# platform_all1.net
KiCad netlist of a schematic drawn in EAGLE
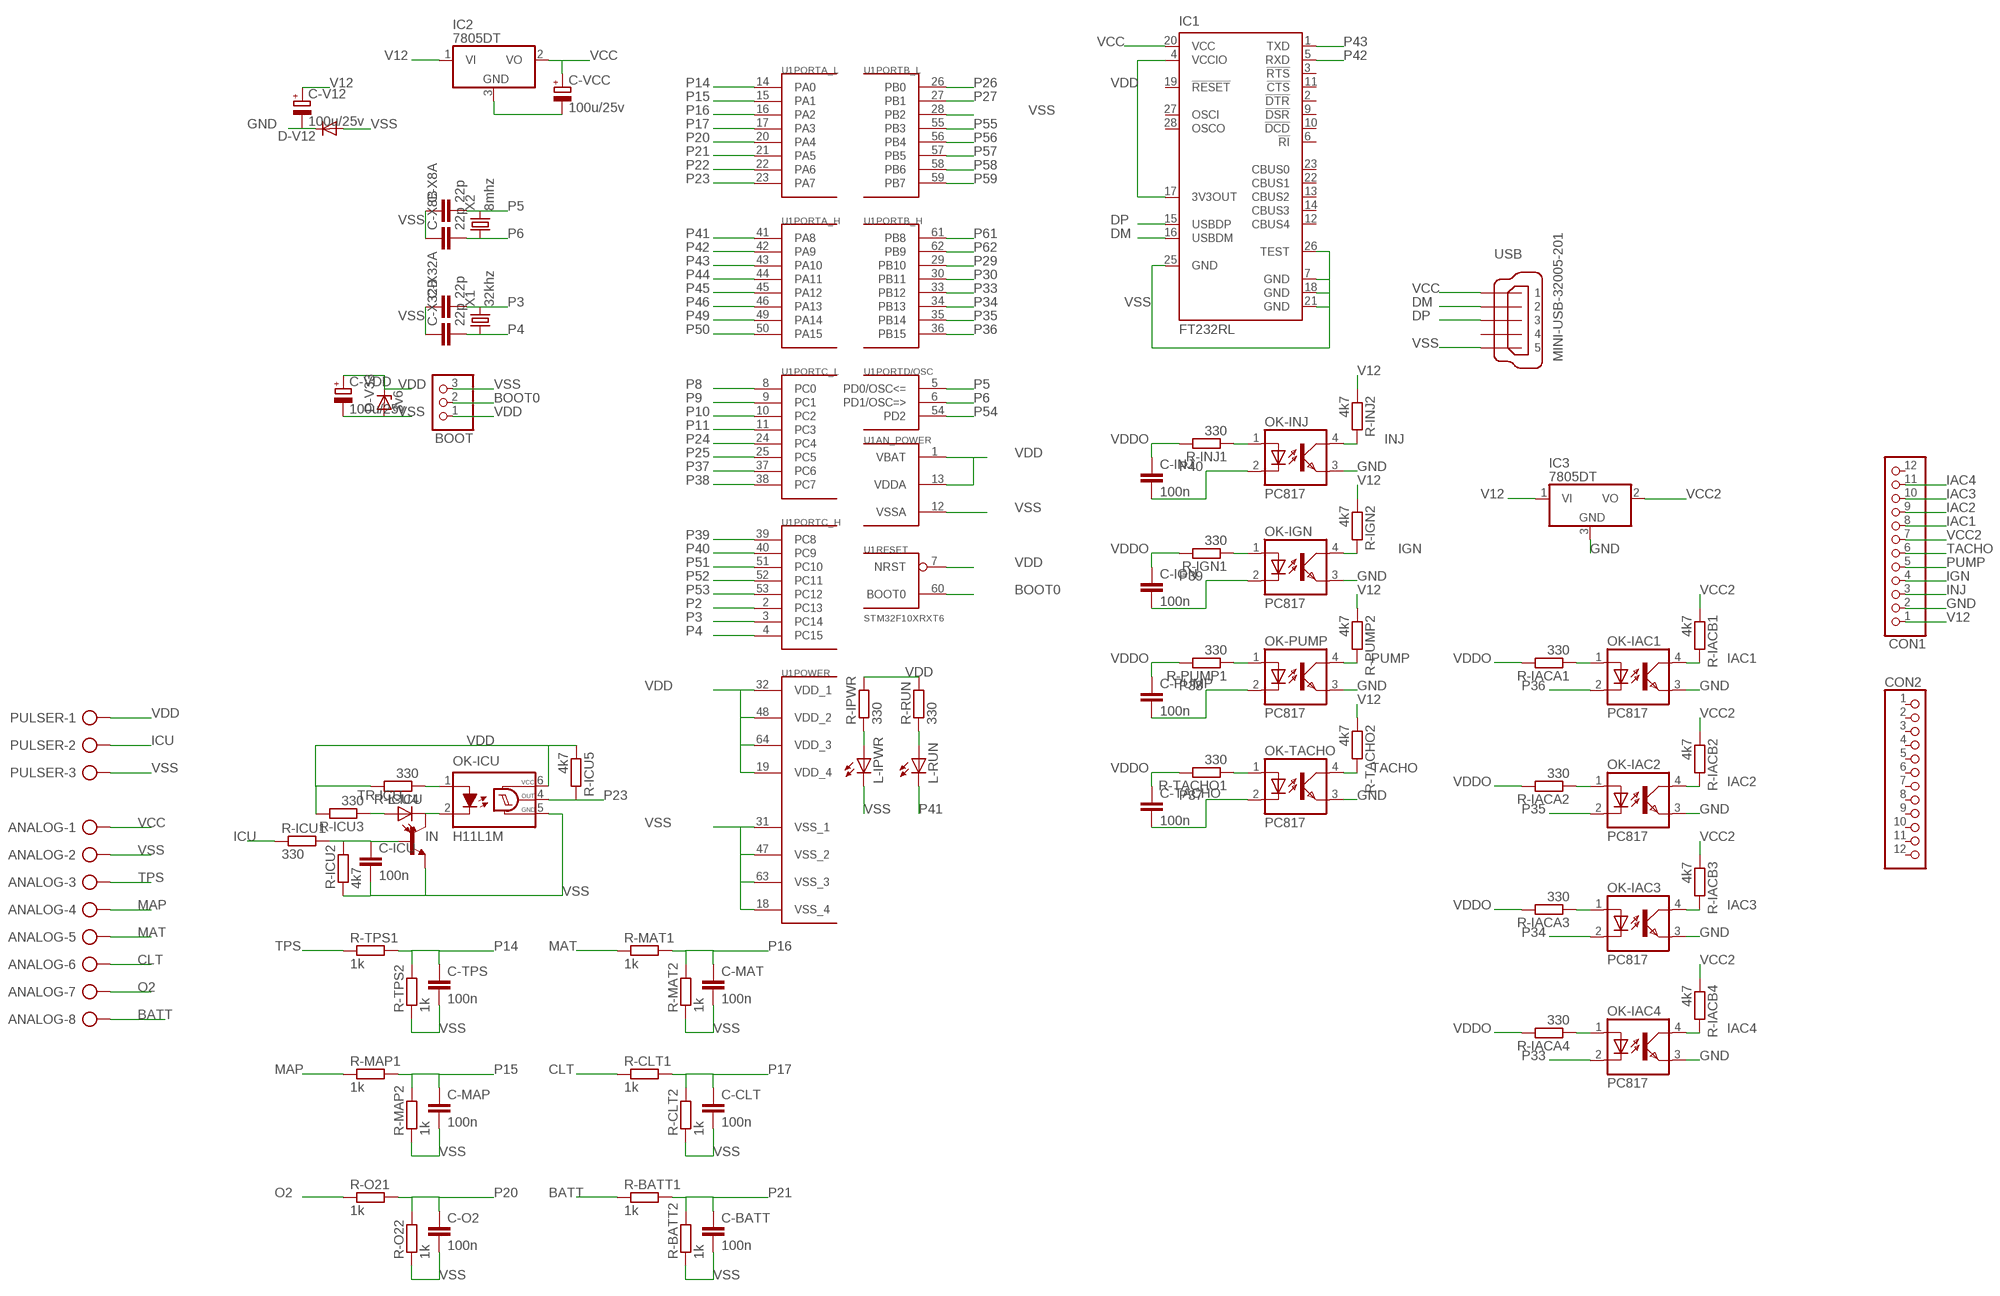
[diagram p0: schematic, sheet 1]

(export (version "E")
  (design (tool "Eeschema 10.0.6"))
  (components
    (comp (ref "ANALOG")
      (value "AK300/8")
      (footprint "eagle-import:AK300_8")
      (libsource (lib "eagle-import") (part "AK300/8"))
    )
    (comp (ref "BOOT")
      (value "PINHD-1X3")
      (footprint "eagle-import:1X03")
      (libsource (lib "eagle-import") (part "PINHD-1X3"))
    )
    (comp (ref "C-BATT")
      (value "100n")
      (footprint "eagle-import:C1206")
      (libsource (lib "eagle-import") (part "C-EUC1206"))
    )
    (comp (ref "C-CLT")
      (value "100n")
      (footprint "eagle-import:C1206")
      (libsource (lib "eagle-import") (part "C-EUC1206"))
    )
    (comp (ref "C-ICU")
      (value "100n")
      (footprint "eagle-import:C1206")
      (libsource (lib "eagle-import") (part "C-EUC1206"))
    )
    (comp (ref "C-IGN")
      (value "100n")
      (footprint "eagle-import:C1206")
      (libsource (lib "eagle-import") (part "C-EUC1206"))
    )
    (comp (ref "C-INJ")
      (value "100n")
      (footprint "eagle-import:C1206")
      (libsource (lib "eagle-import") (part "C-EUC1206"))
    )
    (comp (ref "C-MAP")
      (value "100n")
      (footprint "eagle-import:C1206")
      (libsource (lib "eagle-import") (part "C-EUC1206"))
    )
    (comp (ref "C-MAT")
      (value "100n")
      (footprint "eagle-import:C1206")
      (libsource (lib "eagle-import") (part "C-EUC1206"))
    )
    (comp (ref "C-O2")
      (value "100n")
      (footprint "eagle-import:C1206")
      (libsource (lib "eagle-import") (part "C-EUC1206"))
    )
    (comp (ref "C-PUMP")
      (value "100n")
      (footprint "eagle-import:C1206")
      (libsource (lib "eagle-import") (part "C-EUC1206"))
    )
    (comp (ref "C-TACHO")
      (value "100n")
      (footprint "eagle-import:C1206")
      (libsource (lib "eagle-import") (part "C-EUC1206"))
    )
    (comp (ref "C-TPS")
      (value "100n")
      (footprint "eagle-import:C1206")
      (libsource (lib "eagle-import") (part "C-EUC1206"))
    )
    (comp (ref "C-V12")
      (value "100u/25v")
      (footprint "eagle-import:PANASONIC_D")
      (libsource (lib "eagle-import") (part "CPOL-EUD"))
    )
    (comp (ref "C-VCC")
      (value "100u/25v")
      (footprint "eagle-import:PANASONIC_D")
      (libsource (lib "eagle-import") (part "CPOL-EUD"))
    )
    (comp (ref "C-VDD")
      (value "100u/25v")
      (footprint "eagle-import:PANASONIC_D")
      (libsource (lib "eagle-import") (part "CPOL-EUD"))
    )
    (comp (ref "C-X8A")
      (value "22p")
      (footprint "eagle-import:C1206")
      (libsource (lib "eagle-import") (part "C-EUC1206"))
    )
    (comp (ref "C-X8B")
      (value "22p")
      (footprint "eagle-import:C1206")
      (libsource (lib "eagle-import") (part "C-EUC1206"))
    )
    (comp (ref "C-X32A")
      (value "22p")
      (footprint "eagle-import:C1206")
      (libsource (lib "eagle-import") (part "C-EUC1206"))
    )
    (comp (ref "C-X32B")
      (value "22p")
      (footprint "eagle-import:C1206")
      (libsource (lib "eagle-import") (part "C-EUC1206"))
    )
    (comp (ref "CON1")
      (value "PINHD-1X12")
      (footprint "eagle-import:1X12")
      (libsource (lib "eagle-import") (part "PINHD-1X12"))
    )
    (comp (ref "CON2")
      (value "PINHD-1X12")
      (footprint "eagle-import:1X12")
      (libsource (lib "eagle-import") (part "PINHD-1X12"))
    )
    (comp (ref "D-V12")
      (value "DIODE-SMB")
      (footprint "eagle-import:SMB")
      (libsource (lib "eagle-import") (part "DIODE-SMB"))
    )
    (comp (ref "D-V33")
      (value "3v6")
      (footprint "eagle-import:SMB")
      (libsource (lib "eagle-import") (part "ZENER-DIODESMB"))
    )
    (comp (ref "IC1")
      (value "FT232RL")
      (footprint "eagle-import:SSOP28")
      (libsource (lib "eagle-import") (part "FT232RL"))
    )
    (comp (ref "IC2")
      (value "7805DT")
      (footprint "eagle-import:TO252")
      (libsource (lib "eagle-import") (part "78DT05"))
    )
    (comp (ref "IC3")
      (value "7805DT")
      (footprint "eagle-import:TO252")
      (libsource (lib "eagle-import") (part "78DT05"))
    )
    (comp (ref "L-ICU")
      (value "LEDSMT1206")
      (footprint "eagle-import:1206")
      (libsource (lib "eagle-import") (part "LEDSMT1206"))
    )
    (comp (ref "L-IPWR")
      (value "LEDSMT1206")
      (footprint "eagle-import:1206")
      (libsource (lib "eagle-import") (part "LEDSMT1206"))
    )
    (comp (ref "L-RUN")
      (value "LEDSMT1206")
      (footprint "eagle-import:1206")
      (libsource (lib "eagle-import") (part "LEDSMT1206"))
    )
    (comp (ref "OK-IAC1")
      (value "PC817")
      (footprint "eagle-import:DIL04")
      (fields (field (name "MPN") "PC817X4J000F"))
      (libsource (lib "eagle-import") (part "PC817"))
    )
    (comp (ref "OK-IAC2")
      (value "PC817")
      (footprint "eagle-import:DIL04")
      (fields (field (name "MPN") "PC817X4J000F"))
      (libsource (lib "eagle-import") (part "PC817"))
    )
    (comp (ref "OK-IAC3")
      (value "PC817")
      (footprint "eagle-import:DIL04")
      (fields (field (name "MPN") "PC817X4J000F"))
      (libsource (lib "eagle-import") (part "PC817"))
    )
    (comp (ref "OK-IAC4")
      (value "PC817")
      (footprint "eagle-import:DIL04")
      (fields (field (name "MPN") "PC817X4J000F"))
      (libsource (lib "eagle-import") (part "PC817"))
    )
    (comp (ref "OK-ICU")
      (value "H11L1M")
      (footprint "eagle-import:DIL06")
      (fields (field (name "MF") "FAIRCHILD SEMICONDUCTOR") (field (name "MPN") "H11L1-M"))
      (libsource (lib "eagle-import") (part "H11LM1"))
    )
    (comp (ref "OK-IGN")
      (value "PC817")
      (footprint "eagle-import:DIL04")
      (fields (field (name "MPN") "PC817X4J000F"))
      (libsource (lib "eagle-import") (part "PC817"))
    )
    (comp (ref "OK-INJ")
      (value "PC817")
      (footprint "eagle-import:DIL04")
      (fields (field (name "MPN") "PC817X4J000F"))
      (libsource (lib "eagle-import") (part "PC817"))
    )
    (comp (ref "OK-PUMP")
      (value "PC817")
      (footprint "eagle-import:DIL04")
      (fields (field (name "MPN") "PC817X4J000F"))
      (libsource (lib "eagle-import") (part "PC817"))
    )
    (comp (ref "OK-TACHO")
      (value "PC817")
      (footprint "eagle-import:DIL04")
      (fields (field (name "MPN") "PC817X4J000F"))
      (libsource (lib "eagle-import") (part "PC817"))
    )
    (comp (ref "PULSER")
      (value "AK300/3")
      (footprint "eagle-import:AK300_3")
      (libsource (lib "eagle-import") (part "AK300/3"))
    )
    (comp (ref "R-BATT1")
      (value "1k")
      (footprint "eagle-import:R1206")
      (libsource (lib "eagle-import") (part "R-EU_R1206"))
    )
    (comp (ref "R-BATT2")
      (value "1k")
      (footprint "eagle-import:R1206")
      (libsource (lib "eagle-import") (part "R-EU_R1206"))
    )
    (comp (ref "R-CLT1")
      (value "1k")
      (footprint "eagle-import:R1206")
      (libsource (lib "eagle-import") (part "R-EU_R1206"))
    )
    (comp (ref "R-CLT2")
      (value "1k")
      (footprint "eagle-import:R1206")
      (libsource (lib "eagle-import") (part "R-EU_R1206"))
    )
    (comp (ref "R-IACA1")
      (value "330")
      (footprint "eagle-import:R1206")
      (libsource (lib "eagle-import") (part "R-EU_R1206"))
    )
    (comp (ref "R-IACA2")
      (value "330")
      (footprint "eagle-import:R1206")
      (libsource (lib "eagle-import") (part "R-EU_R1206"))
    )
    (comp (ref "R-IACA3")
      (value "330")
      (footprint "eagle-import:R1206")
      (libsource (lib "eagle-import") (part "R-EU_R1206"))
    )
    (comp (ref "R-IACA4")
      (value "330")
      (footprint "eagle-import:R1206")
      (libsource (lib "eagle-import") (part "R-EU_R1206"))
    )
    (comp (ref "R-IACB1")
      (value "4k7")
      (footprint "eagle-import:R1206")
      (libsource (lib "eagle-import") (part "R-EU_R1206"))
    )
    (comp (ref "R-IACB2")
      (value "4k7")
      (footprint "eagle-import:R1206")
      (libsource (lib "eagle-import") (part "R-EU_R1206"))
    )
    (comp (ref "R-IACB3")
      (value "4k7")
      (footprint "eagle-import:R1206")
      (libsource (lib "eagle-import") (part "R-EU_R1206"))
    )
    (comp (ref "R-IACB4")
      (value "4k7")
      (footprint "eagle-import:R1206")
      (libsource (lib "eagle-import") (part "R-EU_R1206"))
    )
    (comp (ref "R-ICU1")
      (value "330")
      (footprint "eagle-import:R1206")
      (libsource (lib "eagle-import") (part "R-EU_R1206"))
    )
    (comp (ref "R-ICU2")
      (value "4k7")
      (footprint "eagle-import:R1206")
      (libsource (lib "eagle-import") (part "R-EU_R1206"))
    )
    (comp (ref "R-ICU3")
      (value "330")
      (footprint "eagle-import:R1206")
      (libsource (lib "eagle-import") (part "R-EU_R1206"))
    )
    (comp (ref "R-ICU4")
      (value "330")
      (footprint "eagle-import:R1206")
      (libsource (lib "eagle-import") (part "R-EU_R1206"))
    )
    (comp (ref "R-ICU5")
      (value "4k7")
      (footprint "eagle-import:R1206")
      (libsource (lib "eagle-import") (part "R-EU_R1206"))
    )
    (comp (ref "R-IGN1")
      (value "330")
      (footprint "eagle-import:R1206")
      (libsource (lib "eagle-import") (part "R-EU_R1206"))
    )
    (comp (ref "R-IGN2")
      (value "4k7")
      (footprint "eagle-import:R1206")
      (libsource (lib "eagle-import") (part "R-EU_R1206"))
    )
    (comp (ref "R-INJ1")
      (value "330")
      (footprint "eagle-import:R1206")
      (libsource (lib "eagle-import") (part "R-EU_R1206"))
    )
    (comp (ref "R-INJ2")
      (value "4k7")
      (footprint "eagle-import:R1206")
      (libsource (lib "eagle-import") (part "R-EU_R1206"))
    )
    (comp (ref "R-IPWR")
      (value "330")
      (footprint "eagle-import:R1206")
      (libsource (lib "eagle-import") (part "R-EU_R1206"))
    )
    (comp (ref "R-MAP1")
      (value "1k")
      (footprint "eagle-import:R1206")
      (libsource (lib "eagle-import") (part "R-EU_R1206"))
    )
    (comp (ref "R-MAP2")
      (value "1k")
      (footprint "eagle-import:R1206")
      (libsource (lib "eagle-import") (part "R-EU_R1206"))
    )
    (comp (ref "R-MAT1")
      (value "1k")
      (footprint "eagle-import:R1206")
      (libsource (lib "eagle-import") (part "R-EU_R1206"))
    )
    (comp (ref "R-MAT2")
      (value "1k")
      (footprint "eagle-import:R1206")
      (libsource (lib "eagle-import") (part "R-EU_R1206"))
    )
    (comp (ref "R-O21")
      (value "1k")
      (footprint "eagle-import:R1206")
      (libsource (lib "eagle-import") (part "R-EU_R1206"))
    )
    (comp (ref "R-O22")
      (value "1k")
      (footprint "eagle-import:R1206")
      (libsource (lib "eagle-import") (part "R-EU_R1206"))
    )
    (comp (ref "R-PUMP1")
      (value "330")
      (footprint "eagle-import:R1206")
      (libsource (lib "eagle-import") (part "R-EU_R1206"))
    )
    (comp (ref "R-PUMP2")
      (value "4k7")
      (footprint "eagle-import:R1206")
      (libsource (lib "eagle-import") (part "R-EU_R1206"))
    )
    (comp (ref "R-RUN")
      (value "330")
      (footprint "eagle-import:R1206")
      (libsource (lib "eagle-import") (part "R-EU_R1206"))
    )
    (comp (ref "R-TACHO1")
      (value "330")
      (footprint "eagle-import:R1206")
      (libsource (lib "eagle-import") (part "R-EU_R1206"))
    )
    (comp (ref "R-TACHO2")
      (value "4k7")
      (footprint "eagle-import:R1206")
      (libsource (lib "eagle-import") (part "R-EU_R1206"))
    )
    (comp (ref "R-TPS1")
      (value "1k")
      (footprint "eagle-import:R1206")
      (libsource (lib "eagle-import") (part "R-EU_R1206"))
    )
    (comp (ref "R-TPS2")
      (value "1k")
      (footprint "eagle-import:R1206")
      (libsource (lib "eagle-import") (part "R-EU_R1206"))
    )
    (comp (ref "TR-ICU")
      (value "MMBT3904LT1-NPN-SOT23-BEC")
      (footprint "eagle-import:SOT23-BEC")
      (libsource (lib "eagle-import") (part "-NPN-SOT23-BECMMBT3904LT1"))
    )
    (comp (ref "U1")
      (value "STM32F10XRXT6")
      (footprint "eagle-import:TQFP64")
      (libsource (lib "eagle-import") (part "STM32F10XRXT6"))
    )
    (comp (ref "USB")
      (value "MINI-USB-32005-201")
      (footprint "eagle-import:32005-201")
      (libsource (lib "eagle-import") (part "MINI-USB-32005-201"))
    )
    (comp (ref "X1")
      (value "32khz")
      (footprint "eagle-import:TC26V")
      (libsource (lib "eagle-import") (part "CRYSTALTC26V"))
    )
    (comp (ref "X2")
      (value "8mhz")
      (footprint "eagle-import:HC49U-V")
      (libsource (lib "eagle-import") (part "CRYSTALHC49U-V"))
    )
  )
  (nets
    (net (code "1") (name "/BATT") (class "Default")
      (node (ref "ANALOG") (pin "8") (pinfunction "KL_8") (pintype "passive"))
      (node (ref "R-BATT1") (pin "1") (pinfunction "1_1") (pintype "passive"))
    )
    (net (code "2") (name "/BOOT0") (class "Default")
      (node (ref "BOOT") (pin "2") (pinfunction "2_2") (pintype "passive"))
      (node (ref "U1") (pin "60") (pinfunction "BOOT0_60") (pintype "input"))
    )
    (net (code "3") (name "/CLT") (class "Default")
      (node (ref "ANALOG") (pin "6") (pinfunction "KL_6") (pintype "passive"))
      (node (ref "R-CLT1") (pin "1") (pinfunction "1_1") (pintype "passive"))
    )
    (net (code "4") (name "/DM") (class "Default")
      (node (ref "IC1") (pin "16") (pinfunction "USBDM_16") (pintype "bidirectional"))
      (node (ref "USB") (pin "2") (pinfunction "2_2") (pintype "passive"))
    )
    (net (code "5") (name "/DP") (class "Default")
      (node (ref "IC1") (pin "15") (pinfunction "USBDP_15") (pintype "bidirectional"))
      (node (ref "USB") (pin "3") (pinfunction "3_3") (pintype "passive"))
    )
    (net (code "6") (name "/GND") (class "Default")
      (node (ref "C-V12") (pin "-") (pinfunction "-_-") (pintype "passive"))
      (node (ref "CON1") (pin "2") (pinfunction "2_2") (pintype "passive"))
      (node (ref "D-V12") (pin "C") (pinfunction "C_C") (pintype "passive"))
      (node (ref "IC3") (pin "3") (pinfunction "GND_3") (pintype "passive"))
      (node (ref "OK-IAC1") (pin "3") (pinfunction "EMIT_3") (pintype "passive"))
      (node (ref "OK-IAC2") (pin "3") (pinfunction "EMIT_3") (pintype "passive"))
      (node (ref "OK-IAC3") (pin "3") (pinfunction "EMIT_3") (pintype "passive"))
      (node (ref "OK-IAC4") (pin "3") (pinfunction "EMIT_3") (pintype "passive"))
      (node (ref "OK-IGN") (pin "3") (pinfunction "EMIT_3") (pintype "passive"))
      (node (ref "OK-INJ") (pin "3") (pinfunction "EMIT_3") (pintype "passive"))
      (node (ref "OK-PUMP") (pin "3") (pinfunction "EMIT_3") (pintype "passive"))
      (node (ref "OK-TACHO") (pin "3") (pinfunction "EMIT_3") (pintype "passive"))
    )
    (net (code "7") (name "/IAC1") (class "Default")
      (node (ref "CON1") (pin "8") (pinfunction "8_8") (pintype "passive"))
      (node (ref "OK-IAC1") (pin "4") (pinfunction "COL_4") (pintype "passive"))
      (node (ref "R-IACB1") (pin "2") (pinfunction "2_2") (pintype "passive"))
    )
    (net (code "8") (name "/IAC2") (class "Default")
      (node (ref "CON1") (pin "9") (pinfunction "9_9") (pintype "passive"))
      (node (ref "OK-IAC2") (pin "4") (pinfunction "COL_4") (pintype "passive"))
      (node (ref "R-IACB2") (pin "2") (pinfunction "2_2") (pintype "passive"))
    )
    (net (code "9") (name "/IAC3") (class "Default")
      (node (ref "CON1") (pin "10") (pinfunction "10_10") (pintype "passive"))
      (node (ref "OK-IAC3") (pin "4") (pinfunction "COL_4") (pintype "passive"))
      (node (ref "R-IACB3") (pin "2") (pinfunction "2_2") (pintype "passive"))
    )
    (net (code "10") (name "/IAC4") (class "Default")
      (node (ref "CON1") (pin "11") (pinfunction "11_11") (pintype "passive"))
      (node (ref "OK-IAC4") (pin "4") (pinfunction "COL_4") (pintype "passive"))
      (node (ref "R-IACB4") (pin "2") (pinfunction "2_2") (pintype "passive"))
    )
    (net (code "11") (name "/ICU") (class "Default")
      (node (ref "PULSER") (pin "2") (pinfunction "KL_2") (pintype "passive"))
      (node (ref "R-ICU1") (pin "1") (pinfunction "1_1") (pintype "passive"))
    )
    (net (code "12") (name "/IGN") (class "Default")
      (node (ref "CON1") (pin "4") (pinfunction "4_4") (pintype "passive"))
      (node (ref "OK-IGN") (pin "4") (pinfunction "COL_4") (pintype "passive"))
      (node (ref "R-IGN2") (pin "2") (pinfunction "2_2") (pintype "passive"))
    )
    (net (code "13") (name "/IN") (class "Default")
      (node (ref "L-ICU") (pin "C") (pinfunction "C_C") (pintype "passive"))
      (node (ref "OK-ICU") (pin "2") (pinfunction "C_2") (pintype "passive"))
      (node (ref "TR-ICU") (pin "C") (pinfunction "C_C") (pintype "passive"))
    )
    (net (code "14") (name "/INJ") (class "Default")
      (node (ref "CON1") (pin "3") (pinfunction "3_3") (pintype "passive"))
      (node (ref "OK-INJ") (pin "4") (pinfunction "COL_4") (pintype "passive"))
      (node (ref "R-INJ2") (pin "2") (pinfunction "2_2") (pintype "passive"))
    )
    (net (code "15") (name "/MAP") (class "Default")
      (node (ref "ANALOG") (pin "4") (pinfunction "KL_4") (pintype "passive"))
      (node (ref "R-MAP1") (pin "1") (pinfunction "1_1") (pintype "passive"))
    )
    (net (code "16") (name "/MAT") (class "Default")
      (node (ref "ANALOG") (pin "5") (pinfunction "KL_5") (pintype "passive"))
      (node (ref "R-MAT1") (pin "1") (pinfunction "1_1") (pintype "passive"))
    )
    (net (code "17") (name "/O2") (class "Default")
      (node (ref "ANALOG") (pin "7") (pinfunction "KL_7") (pintype "passive"))
      (node (ref "R-O21") (pin "1") (pinfunction "1_1") (pintype "passive"))
    )
    (net (code "18") (name "/P2") (class "Default")
      (node (ref "U1") (pin "2") (pinfunction "PC13_2") (pintype "bidirectional"))
    )
    (net (code "19") (name "/P3") (class "Default")
      (node (ref "C-X32A") (pin "2") (pinfunction "2_2") (pintype "passive"))
      (node (ref "U1") (pin "3") (pinfunction "PC14_3") (pintype "bidirectional"))
      (node (ref "X1") (pin "2") (pinfunction "2_2") (pintype "passive"))
    )
    (net (code "20") (name "/P4") (class "Default")
      (node (ref "C-X32B") (pin "2") (pinfunction "2_2") (pintype "passive"))
      (node (ref "U1") (pin "4") (pinfunction "PC15_4") (pintype "bidirectional"))
      (node (ref "X1") (pin "1") (pinfunction "1_1") (pintype "passive"))
    )
    (net (code "21") (name "/P5") (class "Default")
      (node (ref "C-X8A") (pin "2") (pinfunction "2_2") (pintype "passive"))
      (node (ref "U1") (pin "5") (pinfunction "PD0/OSC<=_5") (pintype "bidirectional"))
      (node (ref "X2") (pin "2") (pinfunction "2_2") (pintype "passive"))
    )
    (net (code "22") (name "/P6") (class "Default")
      (node (ref "C-X8B") (pin "2") (pinfunction "2_2") (pintype "passive"))
      (node (ref "U1") (pin "6") (pinfunction "PD1/OSC=>_6") (pintype "bidirectional"))
      (node (ref "X2") (pin "1") (pinfunction "1_1") (pintype "passive"))
    )
    (net (code "23") (name "/P8") (class "Default")
      (node (ref "U1") (pin "8") (pinfunction "PC0_8") (pintype "bidirectional"))
    )
    (net (code "24") (name "/P9") (class "Default")
      (node (ref "U1") (pin "9") (pinfunction "PC1_9") (pintype "bidirectional"))
    )
    (net (code "25") (name "/P10") (class "Default")
      (node (ref "U1") (pin "10") (pinfunction "PC2_10") (pintype "bidirectional"))
    )
    (net (code "26") (name "/P11") (class "Default")
      (node (ref "U1") (pin "11") (pinfunction "PC3_11") (pintype "bidirectional"))
    )
    (net (code "27") (name "/P14") (class "Default")
      (node (ref "C-TPS") (pin "1") (pinfunction "1_1") (pintype "passive"))
      (node (ref "R-TPS1") (pin "2") (pinfunction "2_2") (pintype "passive"))
      (node (ref "R-TPS2") (pin "2") (pinfunction "2_2") (pintype "passive"))
      (node (ref "U1") (pin "14") (pinfunction "PA0_14") (pintype "bidirectional"))
    )
    (net (code "28") (name "/P15") (class "Default")
      (node (ref "C-MAP") (pin "1") (pinfunction "1_1") (pintype "passive"))
      (node (ref "R-MAP1") (pin "2") (pinfunction "2_2") (pintype "passive"))
      (node (ref "R-MAP2") (pin "2") (pinfunction "2_2") (pintype "passive"))
      (node (ref "U1") (pin "15") (pinfunction "PA1_15") (pintype "bidirectional"))
    )
    (net (code "29") (name "/P16") (class "Default")
      (node (ref "C-MAT") (pin "1") (pinfunction "1_1") (pintype "passive"))
      (node (ref "R-MAT1") (pin "2") (pinfunction "2_2") (pintype "passive"))
      (node (ref "R-MAT2") (pin "2") (pinfunction "2_2") (pintype "passive"))
      (node (ref "U1") (pin "16") (pinfunction "PA2_16") (pintype "bidirectional"))
    )
    (net (code "30") (name "/P17") (class "Default")
      (node (ref "C-CLT") (pin "1") (pinfunction "1_1") (pintype "passive"))
      (node (ref "R-CLT1") (pin "2") (pinfunction "2_2") (pintype "passive"))
      (node (ref "R-CLT2") (pin "2") (pinfunction "2_2") (pintype "passive"))
      (node (ref "U1") (pin "17") (pinfunction "PA3_17") (pintype "bidirectional"))
    )
    (net (code "31") (name "/P20") (class "Default")
      (node (ref "C-O2") (pin "1") (pinfunction "1_1") (pintype "passive"))
      (node (ref "R-O21") (pin "2") (pinfunction "2_2") (pintype "passive"))
      (node (ref "R-O22") (pin "2") (pinfunction "2_2") (pintype "passive"))
      (node (ref "U1") (pin "20") (pinfunction "PA4_20") (pintype "bidirectional"))
    )
    (net (code "32") (name "/P21") (class "Default")
      (node (ref "C-BATT") (pin "1") (pinfunction "1_1") (pintype "passive"))
      (node (ref "R-BATT1") (pin "2") (pinfunction "2_2") (pintype "passive"))
      (node (ref "R-BATT2") (pin "2") (pinfunction "2_2") (pintype "passive"))
      (node (ref "U1") (pin "21") (pinfunction "PA5_21") (pintype "bidirectional"))
    )
    (net (code "33") (name "/P22") (class "Default")
      (node (ref "U1") (pin "22") (pinfunction "PA6_22") (pintype "bidirectional"))
    )
    (net (code "34") (name "/P23") (class "Default")
      (node (ref "OK-ICU") (pin "4") (pinfunction "OUT_4") (pintype "output"))
      (node (ref "R-ICU5") (pin "2") (pinfunction "2_2") (pintype "passive"))
      (node (ref "U1") (pin "23") (pinfunction "PA7_23") (pintype "bidirectional"))
    )
    (net (code "35") (name "/P24") (class "Default")
      (node (ref "U1") (pin "24") (pinfunction "PC4_24") (pintype "bidirectional"))
    )
    (net (code "36") (name "/P25") (class "Default")
      (node (ref "U1") (pin "25") (pinfunction "PC5_25") (pintype "bidirectional"))
    )
    (net (code "37") (name "/P26") (class "Default")
      (node (ref "U1") (pin "26") (pinfunction "PB0_26") (pintype "bidirectional"))
    )
    (net (code "38") (name "/P27") (class "Default")
      (node (ref "U1") (pin "27") (pinfunction "PB1_27") (pintype "bidirectional"))
    )
    (net (code "39") (name "/P29") (class "Default")
      (node (ref "U1") (pin "29") (pinfunction "PB10_29") (pintype "bidirectional"))
    )
    (net (code "40") (name "/P30") (class "Default")
      (node (ref "U1") (pin "30") (pinfunction "PB11_30") (pintype "bidirectional"))
    )
    (net (code "41") (name "/P33") (class "Default")
      (node (ref "OK-IAC4") (pin "2") (pinfunction "C_2") (pintype "passive"))
      (node (ref "U1") (pin "33") (pinfunction "PB12_33") (pintype "bidirectional"))
    )
    (net (code "42") (name "/P34") (class "Default")
      (node (ref "OK-IAC3") (pin "2") (pinfunction "C_2") (pintype "passive"))
      (node (ref "U1") (pin "34") (pinfunction "PB13_34") (pintype "bidirectional"))
    )
    (net (code "43") (name "/P35") (class "Default")
      (node (ref "OK-IAC2") (pin "2") (pinfunction "C_2") (pintype "passive"))
      (node (ref "U1") (pin "35") (pinfunction "PB14_35") (pintype "bidirectional"))
    )
    (net (code "44") (name "/P36") (class "Default")
      (node (ref "OK-IAC1") (pin "2") (pinfunction "C_2") (pintype "passive"))
      (node (ref "U1") (pin "36") (pinfunction "PB15_36") (pintype "bidirectional"))
    )
    (net (code "45") (name "/P37") (class "Default")
      (node (ref "C-TACHO") (pin "2") (pinfunction "2_2") (pintype "passive"))
      (node (ref "OK-TACHO") (pin "2") (pinfunction "C_2") (pintype "passive"))
      (node (ref "U1") (pin "37") (pinfunction "PC6_37") (pintype "bidirectional"))
    )
    (net (code "46") (name "/P38") (class "Default")
      (node (ref "C-PUMP") (pin "2") (pinfunction "2_2") (pintype "passive"))
      (node (ref "OK-PUMP") (pin "2") (pinfunction "C_2") (pintype "passive"))
      (node (ref "U1") (pin "38") (pinfunction "PC7_38") (pintype "bidirectional"))
    )
    (net (code "47") (name "/P39") (class "Default")
      (node (ref "C-IGN") (pin "2") (pinfunction "2_2") (pintype "passive"))
      (node (ref "OK-IGN") (pin "2") (pinfunction "C_2") (pintype "passive"))
      (node (ref "U1") (pin "39") (pinfunction "PC8_39") (pintype "bidirectional"))
    )
    (net (code "48") (name "/P40") (class "Default")
      (node (ref "C-INJ") (pin "2") (pinfunction "2_2") (pintype "passive"))
      (node (ref "OK-INJ") (pin "2") (pinfunction "C_2") (pintype "passive"))
      (node (ref "U1") (pin "40") (pinfunction "PC9_40") (pintype "bidirectional"))
    )
    (net (code "49") (name "/P41") (class "Default")
      (node (ref "L-RUN") (pin "C") (pinfunction "C_C") (pintype "passive"))
      (node (ref "U1") (pin "41") (pinfunction "PA8_41") (pintype "bidirectional"))
    )
    (net (code "50") (name "/P42") (class "Default")
      (node (ref "IC1") (pin "5") (pinfunction "RXD_5") (pintype "input"))
      (node (ref "U1") (pin "42") (pinfunction "PA9_42") (pintype "bidirectional"))
    )
    (net (code "51") (name "/P43") (class "Default")
      (node (ref "IC1") (pin "1") (pinfunction "TXD_1") (pintype "output"))
      (node (ref "U1") (pin "43") (pinfunction "PA10_43") (pintype "bidirectional"))
    )
    (net (code "52") (name "/P44") (class "Default")
      (node (ref "U1") (pin "44") (pinfunction "PA11_44") (pintype "bidirectional"))
    )
    (net (code "53") (name "/P45") (class "Default")
      (node (ref "U1") (pin "45") (pinfunction "PA12_45") (pintype "bidirectional"))
    )
    (net (code "54") (name "/P46") (class "Default")
      (node (ref "U1") (pin "46") (pinfunction "PA13_46") (pintype "bidirectional"))
    )
    (net (code "55") (name "/P49") (class "Default")
      (node (ref "U1") (pin "49") (pinfunction "PA14_49") (pintype "bidirectional"))
    )
    (net (code "56") (name "/P50") (class "Default")
      (node (ref "U1") (pin "50") (pinfunction "PA15_50") (pintype "bidirectional"))
    )
    (net (code "57") (name "/P51") (class "Default")
      (node (ref "U1") (pin "51") (pinfunction "PC10_51") (pintype "bidirectional"))
    )
    (net (code "58") (name "/P52") (class "Default")
      (node (ref "U1") (pin "52") (pinfunction "PC11_52") (pintype "bidirectional"))
    )
    (net (code "59") (name "/P53") (class "Default")
      (node (ref "U1") (pin "53") (pinfunction "PC12_53") (pintype "bidirectional"))
    )
    (net (code "60") (name "/P54") (class "Default")
      (node (ref "U1") (pin "54") (pinfunction "PD2_54") (pintype "bidirectional"))
    )
    (net (code "61") (name "/P55") (class "Default")
      (node (ref "U1") (pin "55") (pinfunction "PB3_55") (pintype "bidirectional"))
    )
    (net (code "62") (name "/P56") (class "Default")
      (node (ref "U1") (pin "56") (pinfunction "PB4_56") (pintype "bidirectional"))
    )
    (net (code "63") (name "/P57") (class "Default")
      (node (ref "U1") (pin "57") (pinfunction "PB5_57") (pintype "bidirectional"))
    )
    (net (code "64") (name "/P58") (class "Default")
      (node (ref "U1") (pin "58") (pinfunction "PB6_58") (pintype "bidirectional"))
    )
    (net (code "65") (name "/P59") (class "Default")
      (node (ref "U1") (pin "59") (pinfunction "PB7_59") (pintype "bidirectional"))
    )
    (net (code "66") (name "/P61") (class "Default")
      (node (ref "U1") (pin "61") (pinfunction "PB8_61") (pintype "bidirectional"))
    )
    (net (code "67") (name "/P62") (class "Default")
      (node (ref "U1") (pin "62") (pinfunction "PB9_62") (pintype "bidirectional"))
    )
    (net (code "68") (name "/PUMP") (class "Default")
      (node (ref "CON1") (pin "5") (pinfunction "5_5") (pintype "passive"))
      (node (ref "OK-PUMP") (pin "4") (pinfunction "COL_4") (pintype "passive"))
      (node (ref "R-PUMP2") (pin "2") (pinfunction "2_2") (pintype "passive"))
    )
    (net (code "69") (name "/TACHO") (class "Default")
      (node (ref "CON1") (pin "6") (pinfunction "6_6") (pintype "passive"))
      (node (ref "OK-TACHO") (pin "4") (pinfunction "COL_4") (pintype "passive"))
      (node (ref "R-TACHO2") (pin "2") (pinfunction "2_2") (pintype "passive"))
    )
    (net (code "70") (name "/TPS") (class "Default")
      (node (ref "ANALOG") (pin "3") (pinfunction "KL_3") (pintype "passive"))
      (node (ref "R-TPS1") (pin "1") (pinfunction "1_1") (pintype "passive"))
    )
    (net (code "71") (name "/V12") (class "Default")
      (node (ref "C-V12") (pin "+") (pinfunction "+_+") (pintype "passive"))
      (node (ref "CON1") (pin "1") (pinfunction "1_1") (pintype "passive"))
      (node (ref "IC2") (pin "1") (pinfunction "VI_1") (pintype "input"))
      (node (ref "IC3") (pin "1") (pinfunction "VI_1") (pintype "input"))
      (node (ref "R-IGN2") (pin "1") (pinfunction "1_1") (pintype "passive"))
      (node (ref "R-INJ2") (pin "1") (pinfunction "1_1") (pintype "passive"))
      (node (ref "R-PUMP2") (pin "1") (pinfunction "1_1") (pintype "passive"))
      (node (ref "R-TACHO2") (pin "1") (pinfunction "1_1") (pintype "passive"))
    )
    (net (code "72") (name "/VCC") (class "Default")
      (node (ref "ANALOG") (pin "1") (pinfunction "KL_1") (pintype "passive"))
      (node (ref "C-VCC") (pin "+") (pinfunction "+_+") (pintype "passive"))
      (node (ref "IC1") (pin "20") (pinfunction "VCC_20") (pintype "power_in"))
      (node (ref "IC2") (pin "2") (pinfunction "VO_2") (pintype "passive"))
      (node (ref "USB") (pin "1") (pinfunction "1_1") (pintype "passive"))
    )
    (net (code "73") (name "/VCC2") (class "Default")
      (node (ref "CON1") (pin "7") (pinfunction "7_7") (pintype "passive"))
      (node (ref "IC3") (pin "2") (pinfunction "VO_2") (pintype "passive"))
      (node (ref "R-IACB1") (pin "1") (pinfunction "1_1") (pintype "passive"))
      (node (ref "R-IACB2") (pin "1") (pinfunction "1_1") (pintype "passive"))
      (node (ref "R-IACB3") (pin "1") (pinfunction "1_1") (pintype "passive"))
      (node (ref "R-IACB4") (pin "1") (pinfunction "1_1") (pintype "passive"))
    )
    (net (code "74") (name "/VDD") (class "Default")
      (node (ref "BOOT") (pin "1") (pinfunction "1_1") (pintype "passive"))
      (node (ref "C-VDD") (pin "+") (pinfunction "+_+") (pintype "passive"))
      (node (ref "D-V33") (pin "C") (pinfunction "C_C") (pintype "passive"))
      (node (ref "IC1") (pin "17") (pinfunction "3V3OUT_17") (pintype "output"))
      (node (ref "IC1") (pin "4") (pinfunction "VCCIO_4") (pintype "power_in"))
      (node (ref "OK-ICU") (pin "6") (pinfunction "VCC_6") (pintype "power_in"))
      (node (ref "PULSER") (pin "1") (pinfunction "KL_1") (pintype "passive"))
      (node (ref "R-ICU3") (pin "2") (pinfunction "2_2") (pintype "passive"))
      (node (ref "R-ICU4") (pin "2") (pinfunction "2_2") (pintype "passive"))
      (node (ref "R-ICU5") (pin "1") (pinfunction "1_1") (pintype "passive"))
      (node (ref "R-IPWR") (pin "2") (pinfunction "2_2") (pintype "passive"))
      (node (ref "R-RUN") (pin "2") (pinfunction "2_2") (pintype "passive"))
      (node (ref "U1") (pin "1") (pinfunction "VBAT_1") (pintype "power_in"))
      (node (ref "U1") (pin "13") (pinfunction "VDDA_13") (pintype "power_in"))
      (node (ref "U1") (pin "19") (pinfunction "VDD_4_19") (pintype "power_in"))
      (node (ref "U1") (pin "32") (pinfunction "VDD_1_32") (pintype "power_in"))
      (node (ref "U1") (pin "48") (pinfunction "VDD_2_48") (pintype "power_in"))
      (node (ref "U1") (pin "64") (pinfunction "VDD_3_64") (pintype "power_in"))
      (node (ref "U1") (pin "7") (pinfunction "NRST_7") (pintype "input"))
    )
    (net (code "75") (name "/VDDO") (class "Default")
      (node (ref "C-IGN") (pin "1") (pinfunction "1_1") (pintype "passive"))
      (node (ref "C-INJ") (pin "1") (pinfunction "1_1") (pintype "passive"))
      (node (ref "C-PUMP") (pin "1") (pinfunction "1_1") (pintype "passive"))
      (node (ref "C-TACHO") (pin "1") (pinfunction "1_1") (pintype "passive"))
      (node (ref "R-IACA1") (pin "2") (pinfunction "2_2") (pintype "passive"))
      (node (ref "R-IACA2") (pin "2") (pinfunction "2_2") (pintype "passive"))
      (node (ref "R-IACA3") (pin "2") (pinfunction "2_2") (pintype "passive"))
      (node (ref "R-IACA4") (pin "2") (pinfunction "2_2") (pintype "passive"))
      (node (ref "R-IGN1") (pin "2") (pinfunction "2_2") (pintype "passive"))
      (node (ref "R-INJ1") (pin "2") (pinfunction "2_2") (pintype "passive"))
      (node (ref "R-PUMP1") (pin "2") (pinfunction "2_2") (pintype "passive"))
      (node (ref "R-TACHO1") (pin "2") (pinfunction "2_2") (pintype "passive"))
    )
    (net (code "76") (name "/VSS") (class "Default")
      (node (ref "ANALOG") (pin "2") (pinfunction "KL_2") (pintype "passive"))
      (node (ref "BOOT") (pin "3") (pinfunction "3_3") (pintype "passive"))
      (node (ref "C-BATT") (pin "2") (pinfunction "2_2") (pintype "passive"))
      (node (ref "C-CLT") (pin "2") (pinfunction "2_2") (pintype "passive"))
      (node (ref "C-ICU") (pin "2") (pinfunction "2_2") (pintype "passive"))
      (node (ref "C-MAP") (pin "2") (pinfunction "2_2") (pintype "passive"))
      (node (ref "C-MAT") (pin "2") (pinfunction "2_2") (pintype "passive"))
      (node (ref "C-O2") (pin "2") (pinfunction "2_2") (pintype "passive"))
      (node (ref "C-TPS") (pin "2") (pinfunction "2_2") (pintype "passive"))
      (node (ref "C-VCC") (pin "-") (pinfunction "-_-") (pintype "passive"))
      (node (ref "C-VDD") (pin "-") (pinfunction "-_-") (pintype "passive"))
      (node (ref "C-X32A") (pin "1") (pinfunction "1_1") (pintype "passive"))
      (node (ref "C-X32B") (pin "1") (pinfunction "1_1") (pintype "passive"))
      (node (ref "C-X8A") (pin "1") (pinfunction "1_1") (pintype "passive"))
      (node (ref "C-X8B") (pin "1") (pinfunction "1_1") (pintype "passive"))
      (node (ref "D-V12") (pin "A") (pinfunction "A_A") (pintype "passive"))
      (node (ref "D-V33") (pin "A") (pinfunction "A_A") (pintype "passive"))
      (node (ref "IC1") (pin "18") (pinfunction "GND_18") (pintype "power_in"))
      (node (ref "IC1") (pin "21") (pinfunction "GND_21") (pintype "power_in"))
      (node (ref "IC1") (pin "25") (pinfunction "GND_25") (pintype "power_in"))
      (node (ref "IC1") (pin "26") (pinfunction "TEST_26") (pintype "input"))
      (node (ref "IC1") (pin "7") (pinfunction "GND_7") (pintype "power_in"))
      (node (ref "IC2") (pin "3") (pinfunction "GND_3") (pintype "passive"))
      (node (ref "L-IPWR") (pin "C") (pinfunction "C_C") (pintype "passive"))
      (node (ref "OK-ICU") (pin "5") (pinfunction "GND_5") (pintype "power_in"))
      (node (ref "PULSER") (pin "3") (pinfunction "KL_3") (pintype "passive"))
      (node (ref "R-BATT2") (pin "1") (pinfunction "1_1") (pintype "passive"))
      (node (ref "R-CLT2") (pin "1") (pinfunction "1_1") (pintype "passive"))
      (node (ref "R-ICU2") (pin "1") (pinfunction "1_1") (pintype "passive"))
      (node (ref "R-MAP2") (pin "1") (pinfunction "1_1") (pintype "passive"))
      (node (ref "R-MAT2") (pin "1") (pinfunction "1_1") (pintype "passive"))
      (node (ref "R-O22") (pin "1") (pinfunction "1_1") (pintype "passive"))
      (node (ref "R-TPS2") (pin "1") (pinfunction "1_1") (pintype "passive"))
      (node (ref "TR-ICU") (pin "E") (pinfunction "E_E") (pintype "passive"))
      (node (ref "U1") (pin "12") (pinfunction "VSSA_12") (pintype "power_in"))
      (node (ref "U1") (pin "18") (pinfunction "VSS_4_18") (pintype "power_in"))
      (node (ref "U1") (pin "28") (pinfunction "PB2_28") (pintype "bidirectional"))
      (node (ref "U1") (pin "31") (pinfunction "VSS_1_31") (pintype "power_in"))
      (node (ref "U1") (pin "47") (pinfunction "VSS_2_47") (pintype "power_in"))
      (node (ref "U1") (pin "63") (pinfunction "VSS_3_63") (pintype "power_in"))
      (node (ref "USB") (pin "5") (pinfunction "5_5") (pintype "passive"))
    )
    (net (code "77") (name "Net-(C-ICU-Pad1)") (class "Default")
      (node (ref "C-ICU") (pin "1") (pinfunction "1_1") (pintype "passive"))
      (node (ref "R-ICU1") (pin "2") (pinfunction "2_2") (pintype "passive"))
      (node (ref "R-ICU2") (pin "2") (pinfunction "2_2") (pintype "passive"))
      (node (ref "TR-ICU") (pin "B") (pinfunction "B_B") (pintype "passive"))
    )
    (net (code "78") (name "Net-(L-ICU-PadA)") (class "Default")
      (node (ref "L-ICU") (pin "A") (pinfunction "A_A") (pintype "passive"))
      (node (ref "R-ICU3") (pin "1") (pinfunction "1_1") (pintype "passive"))
    )
    (net (code "79") (name "Net-(L-IPWR-PadA)") (class "Default")
      (node (ref "L-IPWR") (pin "A") (pinfunction "A_A") (pintype "passive"))
      (node (ref "R-IPWR") (pin "1") (pinfunction "1_1") (pintype "passive"))
    )
    (net (code "80") (name "Net-(L-RUN-PadA)") (class "Default")
      (node (ref "L-RUN") (pin "A") (pinfunction "A_A") (pintype "passive"))
      (node (ref "R-RUN") (pin "1") (pinfunction "1_1") (pintype "passive"))
    )
    (net (code "81") (name "Net-(OK-IAC1-A)") (class "Default")
      (node (ref "OK-IAC1") (pin "1") (pinfunction "A_1") (pintype "passive"))
      (node (ref "R-IACA1") (pin "1") (pinfunction "1_1") (pintype "passive"))
    )
    (net (code "82") (name "Net-(OK-IAC2-A)") (class "Default")
      (node (ref "OK-IAC2") (pin "1") (pinfunction "A_1") (pintype "passive"))
      (node (ref "R-IACA2") (pin "1") (pinfunction "1_1") (pintype "passive"))
    )
    (net (code "83") (name "Net-(OK-IAC3-A)") (class "Default")
      (node (ref "OK-IAC3") (pin "1") (pinfunction "A_1") (pintype "passive"))
      (node (ref "R-IACA3") (pin "1") (pinfunction "1_1") (pintype "passive"))
    )
    (net (code "84") (name "Net-(OK-IAC4-A)") (class "Default")
      (node (ref "OK-IAC4") (pin "1") (pinfunction "A_1") (pintype "passive"))
      (node (ref "R-IACA4") (pin "1") (pinfunction "1_1") (pintype "passive"))
    )
    (net (code "85") (name "Net-(OK-ICU-A)") (class "Default")
      (node (ref "OK-ICU") (pin "1") (pinfunction "A_1") (pintype "passive"))
      (node (ref "R-ICU4") (pin "1") (pinfunction "1_1") (pintype "passive"))
    )
    (net (code "86") (name "Net-(OK-IGN-A)") (class "Default")
      (node (ref "OK-IGN") (pin "1") (pinfunction "A_1") (pintype "passive"))
      (node (ref "R-IGN1") (pin "1") (pinfunction "1_1") (pintype "passive"))
    )
    (net (code "87") (name "Net-(OK-INJ-A)") (class "Default")
      (node (ref "OK-INJ") (pin "1") (pinfunction "A_1") (pintype "passive"))
      (node (ref "R-INJ1") (pin "1") (pinfunction "1_1") (pintype "passive"))
    )
    (net (code "88") (name "Net-(OK-PUMP-A)") (class "Default")
      (node (ref "OK-PUMP") (pin "1") (pinfunction "A_1") (pintype "passive"))
      (node (ref "R-PUMP1") (pin "1") (pinfunction "1_1") (pintype "passive"))
    )
    (net (code "89") (name "Net-(OK-TACHO-A)") (class "Default")
      (node (ref "OK-TACHO") (pin "1") (pinfunction "A_1") (pintype "passive"))
      (node (ref "R-TACHO1") (pin "1") (pinfunction "1_1") (pintype "passive"))
    )
    (net (code "90") (name "unconnected-(CON1-Pad12)") (class "Default")
      (node (ref "CON1") (pin "12") (pinfunction "12_12") (pintype "passive"))
    )
    (net (code "91") (name "unconnected-(CON2-Pad1)") (class "Default")
      (node (ref "CON2") (pin "1") (pinfunction "1_1") (pintype "passive"))
    )
    (net (code "92") (name "unconnected-(CON2-Pad2)") (class "Default")
      (node (ref "CON2") (pin "2") (pinfunction "2_2") (pintype "passive"))
    )
    (net (code "93") (name "unconnected-(CON2-Pad3)") (class "Default")
      (node (ref "CON2") (pin "3") (pinfunction "3_3") (pintype "passive"))
    )
    (net (code "94") (name "unconnected-(CON2-Pad4)") (class "Default")
      (node (ref "CON2") (pin "4") (pinfunction "4_4") (pintype "passive"))
    )
    (net (code "95") (name "unconnected-(CON2-Pad5)") (class "Default")
      (node (ref "CON2") (pin "5") (pinfunction "5_5") (pintype "passive"))
    )
    (net (code "96") (name "unconnected-(CON2-Pad6)") (class "Default")
      (node (ref "CON2") (pin "6") (pinfunction "6_6") (pintype "passive"))
    )
    (net (code "97") (name "unconnected-(CON2-Pad7)") (class "Default")
      (node (ref "CON2") (pin "7") (pinfunction "7_7") (pintype "passive"))
    )
    (net (code "98") (name "unconnected-(CON2-Pad8)") (class "Default")
      (node (ref "CON2") (pin "8") (pinfunction "8_8") (pintype "passive"))
    )
    (net (code "99") (name "unconnected-(CON2-Pad9)") (class "Default")
      (node (ref "CON2") (pin "9") (pinfunction "9_9") (pintype "passive"))
    )
    (net (code "100") (name "unconnected-(CON2-Pad10)") (class "Default")
      (node (ref "CON2") (pin "10") (pinfunction "10_10") (pintype "passive"))
    )
    (net (code "101") (name "unconnected-(CON2-Pad11)") (class "Default")
      (node (ref "CON2") (pin "11") (pinfunction "11_11") (pintype "passive"))
    )
    (net (code "102") (name "unconnected-(CON2-Pad12)") (class "Default")
      (node (ref "CON2") (pin "12") (pinfunction "12_12") (pintype "passive"))
    )
    (net (code "103") (name "unconnected-(IC1-CBUS0-Pad23)") (class "Default")
      (node (ref "IC1") (pin "23") (pinfunction "CBUS0_23") (pintype "bidirectional"))
    )
    (net (code "104") (name "unconnected-(IC1-CBUS1-Pad22)") (class "Default")
      (node (ref "IC1") (pin "22") (pinfunction "CBUS1_22") (pintype "bidirectional"))
    )
    (net (code "105") (name "unconnected-(IC1-CBUS2-Pad13)") (class "Default")
      (node (ref "IC1") (pin "13") (pinfunction "CBUS2_13") (pintype "bidirectional"))
    )
    (net (code "106") (name "unconnected-(IC1-CBUS3-Pad14)") (class "Default")
      (node (ref "IC1") (pin "14") (pinfunction "CBUS3_14") (pintype "bidirectional"))
    )
    (net (code "107") (name "unconnected-(IC1-CBUS4-Pad12)") (class "Default")
      (node (ref "IC1") (pin "12") (pinfunction "CBUS4_12") (pintype "bidirectional"))
    )
    (net (code "108") (name "unconnected-(IC1-OSCI-Pad27)") (class "Default")
      (node (ref "IC1") (pin "27") (pinfunction "OSCI_27") (pintype "input"))
    )
    (net (code "109") (name "unconnected-(IC1-OSCO-Pad28)") (class "Default")
      (node (ref "IC1") (pin "28") (pinfunction "OSCO_28") (pintype "output"))
    )
    (net (code "110") (name "unconnected-(IC1-~{CTS}-Pad11)") (class "Default")
      (node (ref "IC1") (pin "11") (pinfunction "~{CTS}_11") (pintype "input"))
    )
    (net (code "111") (name "unconnected-(IC1-~{DCD}-Pad10)") (class "Default")
      (node (ref "IC1") (pin "10") (pinfunction "~{DCD}_10") (pintype "input"))
    )
    (net (code "112") (name "unconnected-(IC1-~{DSR}-Pad9)") (class "Default")
      (node (ref "IC1") (pin "9") (pinfunction "~{DSR}_9") (pintype "input"))
    )
    (net (code "113") (name "unconnected-(IC1-~{DTR}-Pad2)") (class "Default")
      (node (ref "IC1") (pin "2") (pinfunction "~{DTR}_2") (pintype "output"))
    )
    (net (code "114") (name "unconnected-(IC1-~{RESET}-Pad19)") (class "Default")
      (node (ref "IC1") (pin "19") (pinfunction "~{RESET}_19") (pintype "input"))
    )
    (net (code "115") (name "unconnected-(IC1-~{RI}-Pad6)") (class "Default")
      (node (ref "IC1") (pin "6") (pinfunction "~{RI}_6") (pintype "input"))
    )
    (net (code "116") (name "unconnected-(IC1-~{RTS}-Pad3)") (class "Default")
      (node (ref "IC1") (pin "3") (pinfunction "~{RTS}_3") (pintype "output"))
    )
    (net (code "117") (name "unconnected-(USB-Pad4)") (class "Default")
      (node (ref "USB") (pin "4") (pinfunction "4_4") (pintype "passive"))
    )
  )
)
